# vdc_signal_adaptation.net
KiCad netlist of a schematic drawn in Altium Designer
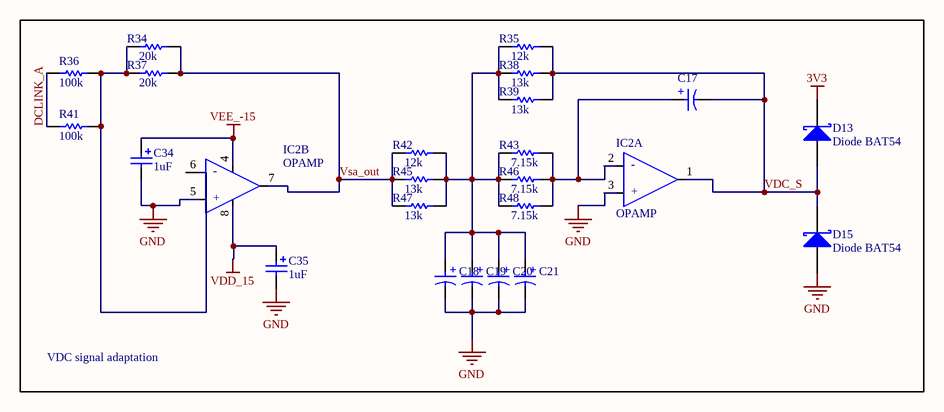
[diagram p0: vdc_signal_adaptation.SchDoc]

(export (version "E")
  (design (tool "Eeschema 10.0.6"))
  (components
    (comp (ref "C17")
      (value "860020772005")
      (footprint "WCAP-ATG5_D5H11")
      (description "860020772005 Cap Aluminum Lytic 1uF 63V 20% (5 X 11mm) Radial 2mm 13mA 2000h 105C")
      (fields (field (name "TOLERANCE") "20%"))
      (libsource (lib "Altium Content Vault") (part "Capacitor_Polarized"))
    )
    (comp (ref "C18")
      (value "860020772005")
      (footprint "WCAP-ATG5_D5H11")
      (description "860020772005 Cap Aluminum Lytic 1uF 63V 20% (5 X 11mm) Radial 2mm 13mA 2000h 105C")
      (fields (field (name "TOLERANCE") "20%"))
      (libsource (lib "Altium Content Vault") (part "Capacitor_Polarized"))
    )
    (comp (ref "C19")
      (value "860020772005")
      (footprint "WCAP-ATG5_D5H11")
      (description "860020772005 Cap Aluminum Lytic 1uF 63V 20% (5 X 11mm) Radial 2mm 13mA 2000h 105C")
      (fields (field (name "TOLERANCE") "20%"))
      (libsource (lib "Altium Content Vault") (part "Capacitor_Polarized"))
    )
    (comp (ref "C20")
      (value "860020772005")
      (footprint "WCAP-ATG5_D5H11")
      (description "860020772005 Cap Aluminum Lytic 1uF 63V 20% (5 X 11mm) Radial 2mm 13mA 2000h 105C")
      (fields (field (name "TOLERANCE") "20%"))
      (libsource (lib "Altium Content Vault") (part "Capacitor_Polarized"))
    )
    (comp (ref "C21")
      (value "860020772005")
      (footprint "WCAP-ATG5_D5H11")
      (description "860020772005 Cap Aluminum Lytic 1uF 63V 20% (5 X 11mm) Radial 2mm 13mA 2000h 105C")
      (fields (field (name "TOLERANCE") "20%"))
      (libsource (lib "Altium Content Vault") (part "Capacitor_Polarized"))
    )
    (comp (ref "C34")
      (value "1uF")
      (footprint "RAD-0.1")
      (description "Polarized Capacitor (Radial)")
      (fields (field (name "Comment") "Cap No Pol") (field (name "PUBLISHER") "Altium Limited"))
      (libsource (lib "LABSTEPS_Project") (part "Cap No Pol"))
    )
    (comp (ref "C35")
      (value "1uF")
      (footprint "RAD-0.1")
      (description "Polarized Capacitor (Radial)")
      (fields (field (name "Comment") "Cap No Pol") (field (name "PUBLISHER") "Altium Limited"))
      (libsource (lib "LABSTEPS_Project") (part "Cap No Pol"))
    )
    (comp (ref "D13")
      (value "Diode BAT54")
      (footprint "DO-204AL")
      (description "Schottky Rectifier")
      (fields (field (name "PUBLISHER") "Altium Limited"))
      (libsource (lib "LABSTEPS_Project") (part "Diode 11DQ03"))
    )
    (comp (ref "D15")
      (value "Diode BAT54")
      (footprint "DO-204AL")
      (description "Schottky Rectifier")
      (fields (field (name "PUBLISHER") "Altium Limited"))
      (libsource (lib "LABSTEPS_Project") (part "Diode 11DQ03"))
    )
    (comp (ref "IC2")
      (value "OPAMP")
      (footprint "DIP-8")
      (description "ADTL082")
      (libsource (lib "LABSTEPS_Project") (part "ADTL082"))
    )
    (comp (ref "R34")
      (value "20k")
      (footprint "AXIAL-0.4")
      (description "Resistor")
      (fields (field (name "Comment") "Res1") (field (name "PUBLISHER") "Altium Limited"))
      (libsource (lib "Miscellaneous Devices") (part "Res1"))
    )
    (comp (ref "R35")
      (value "12k")
      (footprint "AXIAL-0.4")
      (description "Resistor")
      (fields (field (name "Comment") "Res1") (field (name "PUBLISHER") "Altium Limited"))
      (libsource (lib "Miscellaneous Devices") (part "Res1"))
    )
    (comp (ref "R36")
      (value "100k")
      (footprint "AXIAL-0.4")
      (description "Resistor")
      (fields (field (name "PUBLISHER") "Altium Limited"))
      (libsource (lib "Miscellaneous Devices") (part "Res1"))
    )
    (comp (ref "R37")
      (value "20k")
      (footprint "AXIAL-0.4")
      (description "Resistor")
      (fields (field (name "Comment") "Res1") (field (name "PUBLISHER") "Altium Limited"))
      (libsource (lib "Miscellaneous Devices") (part "Res1"))
    )
    (comp (ref "R38")
      (value "13k")
      (footprint "AXIAL-0.4")
      (description "Resistor")
      (fields (field (name "Comment") "Res1") (field (name "PUBLISHER") "Altium Limited"))
      (libsource (lib "Miscellaneous Devices") (part "Res1"))
    )
    (comp (ref "R39")
      (value "13k")
      (footprint "AXIAL-0.4")
      (description "Resistor")
      (fields (field (name "Comment") "Res1") (field (name "PUBLISHER") "Altium Limited"))
      (libsource (lib "Miscellaneous Devices") (part "Res1"))
    )
    (comp (ref "R41")
      (value "100k")
      (footprint "AXIAL-0.4")
      (description "Resistor")
      (fields (field (name "Comment") "Res1") (field (name "PUBLISHER") "Altium Limited"))
      (libsource (lib "Miscellaneous Devices") (part "Res1"))
    )
    (comp (ref "R42")
      (value "12k")
      (footprint "AXIAL-0.4")
      (description "Resistor")
      (fields (field (name "Comment") "Res1") (field (name "PUBLISHER") "Altium Limited"))
      (libsource (lib "Miscellaneous Devices") (part "Res1"))
    )
    (comp (ref "R43")
      (value "7.15k")
      (footprint "AXIAL-0.4")
      (description "Resistor")
      (fields (field (name "Comment") "Res1") (field (name "PUBLISHER") "Altium Limited"))
      (libsource (lib "Miscellaneous Devices") (part "Res1"))
    )
    (comp (ref "R45")
      (value "13k")
      (footprint "AXIAL-0.4")
      (description "Resistor")
      (fields (field (name "Comment") "Res1") (field (name "PUBLISHER") "Altium Limited"))
      (libsource (lib "Miscellaneous Devices") (part "Res1"))
    )
    (comp (ref "R46")
      (value "7.15k")
      (footprint "AXIAL-0.4")
      (description "Resistor")
      (fields (field (name "Comment") "Res1") (field (name "PUBLISHER") "Altium Limited"))
      (libsource (lib "Miscellaneous Devices") (part "Res1"))
    )
    (comp (ref "R47")
      (value "13k")
      (footprint "AXIAL-0.4")
      (description "Resistor")
      (fields (field (name "Comment") "Res1") (field (name "PUBLISHER") "Altium Limited"))
      (libsource (lib "Miscellaneous Devices") (part "Res1"))
    )
    (comp (ref "R48")
      (value "7.15k")
      (footprint "AXIAL-0.4")
      (description "Resistor")
      (fields (field (name "Comment") "Res1") (field (name "PUBLISHER") "Altium Limited"))
      (libsource (lib "Miscellaneous Devices") (part "Res1"))
    )
  )
  (nets
    (net (code "1") (name "/DCLINK_A") (class "Default")
      (node (ref "R36") (pin "1") (pinfunction "1_1") (pintype "passive"))
      (node (ref "R41") (pin "1") (pinfunction "1_1") (pintype "passive"))
    )
    (net (code "2") (name "/VDC_S") (class "Default")
      (node (ref "C17") (pin "2") (pinfunction "N_2") (pintype "passive"))
      (node (ref "D13") (pin "1") (pinfunction "A_1") (pintype "passive"))
      (node (ref "D15") (pin "2") (pinfunction "K_2") (pintype "passive"))
      (node (ref "IC2") (pin "1") (pinfunction "OUT_A_1") (pintype "passive"))
      (node (ref "R35") (pin "2") (pinfunction "2_2") (pintype "passive"))
      (node (ref "R38") (pin "2") (pinfunction "2_2") (pintype "passive"))
      (node (ref "R39") (pin "2") (pinfunction "2_2") (pintype "passive"))
    )
    (net (code "3") (name "/Vsa_out") (class "Default")
      (node (ref "IC2") (pin "7") (pinfunction "OUT_B_7") (pintype "passive"))
      (node (ref "R34") (pin "2") (pinfunction "2_2") (pintype "passive"))
      (node (ref "R37") (pin "2") (pinfunction "2_2") (pintype "passive"))
      (node (ref "R42") (pin "1") (pinfunction "1_1") (pintype "passive"))
      (node (ref "R45") (pin "1") (pinfunction "1_1") (pintype "passive"))
      (node (ref "R47") (pin "1") (pinfunction "1_1") (pintype "passive"))
    )
    (net (code "4") (name "3V3") (class "Default")
      (node (ref "D13") (pin "2") (pinfunction "K_2") (pintype "passive"))
    )
    (net (code "5") (name "GND") (class "Default")
      (node (ref "C18") (pin "2") (pinfunction "N_2") (pintype "passive"))
      (node (ref "C19") (pin "2") (pinfunction "N_2") (pintype "passive"))
      (node (ref "C20") (pin "2") (pinfunction "N_2") (pintype "passive"))
      (node (ref "C21") (pin "2") (pinfunction "N_2") (pintype "passive"))
      (node (ref "C34") (pin "2") (pinfunction "2_2") (pintype "passive"))
      (node (ref "C35") (pin "2") (pinfunction "2_2") (pintype "passive"))
      (node (ref "D15") (pin "1") (pinfunction "A_1") (pintype "passive"))
      (node (ref "IC2") (pin "3") (pinfunction "IN_A_+_3") (pintype "passive"))
      (node (ref "IC2") (pin "5") (pinfunction "IN_B_+_5") (pintype "passive"))
    )
    (net (code "6") (name "Net-(C17-P)") (class "Default")
      (node (ref "C17") (pin "1") (pinfunction "P_1") (pintype "passive"))
      (node (ref "IC2") (pin "2") (pinfunction "IN_A_-_2") (pintype "passive"))
      (node (ref "R43") (pin "2") (pinfunction "2_2") (pintype "passive"))
      (node (ref "R46") (pin "2") (pinfunction "2_2") (pintype "passive"))
      (node (ref "R48") (pin "2") (pinfunction "2_2") (pintype "passive"))
    )
    (net (code "7") (name "Net-(C18-P)") (class "Default")
      (node (ref "C18") (pin "1") (pinfunction "P_1") (pintype "passive"))
      (node (ref "C19") (pin "1") (pinfunction "P_1") (pintype "passive"))
      (node (ref "C20") (pin "1") (pinfunction "P_1") (pintype "passive"))
      (node (ref "C21") (pin "1") (pinfunction "P_1") (pintype "passive"))
      (node (ref "R35") (pin "1") (pinfunction "1_1") (pintype "passive"))
      (node (ref "R38") (pin "1") (pinfunction "1_1") (pintype "passive"))
      (node (ref "R39") (pin "1") (pinfunction "1_1") (pintype "passive"))
      (node (ref "R42") (pin "2") (pinfunction "2_2") (pintype "passive"))
      (node (ref "R43") (pin "1") (pinfunction "1_1") (pintype "passive"))
      (node (ref "R45") (pin "2") (pinfunction "2_2") (pintype "passive"))
      (node (ref "R46") (pin "1") (pinfunction "1_1") (pintype "passive"))
      (node (ref "R47") (pin "2") (pinfunction "2_2") (pintype "passive"))
      (node (ref "R48") (pin "1") (pinfunction "1_1") (pintype "passive"))
    )
    (net (code "8") (name "Net-(IC2B-IN_B_-)") (class "Default")
      (node (ref "IC2") (pin "6") (pinfunction "IN_B_-_6") (pintype "passive"))
      (node (ref "R34") (pin "1") (pinfunction "1_1") (pintype "passive"))
      (node (ref "R36") (pin "2") (pinfunction "2_2") (pintype "passive"))
      (node (ref "R37") (pin "1") (pinfunction "1_1") (pintype "passive"))
      (node (ref "R41") (pin "2") (pinfunction "2_2") (pintype "passive"))
    )
    (net (code "9") (name "VDD_15") (class "Default")
      (node (ref "C35") (pin "1") (pinfunction "1_1") (pintype "passive"))
      (node (ref "IC2") (pin "8") (pinfunction "V+_8") (pintype "passive"))
    )
    (net (code "10") (name "VEE_-15") (class "Default")
      (node (ref "C34") (pin "1") (pinfunction "1_1") (pintype "passive"))
      (node (ref "IC2") (pin "4") (pinfunction "-V_4") (pintype "passive"))
    )
  )
)
